# RPI_CAM_INTERFACE.net
KiCad netlist of a schematic drawn in Altium Designer
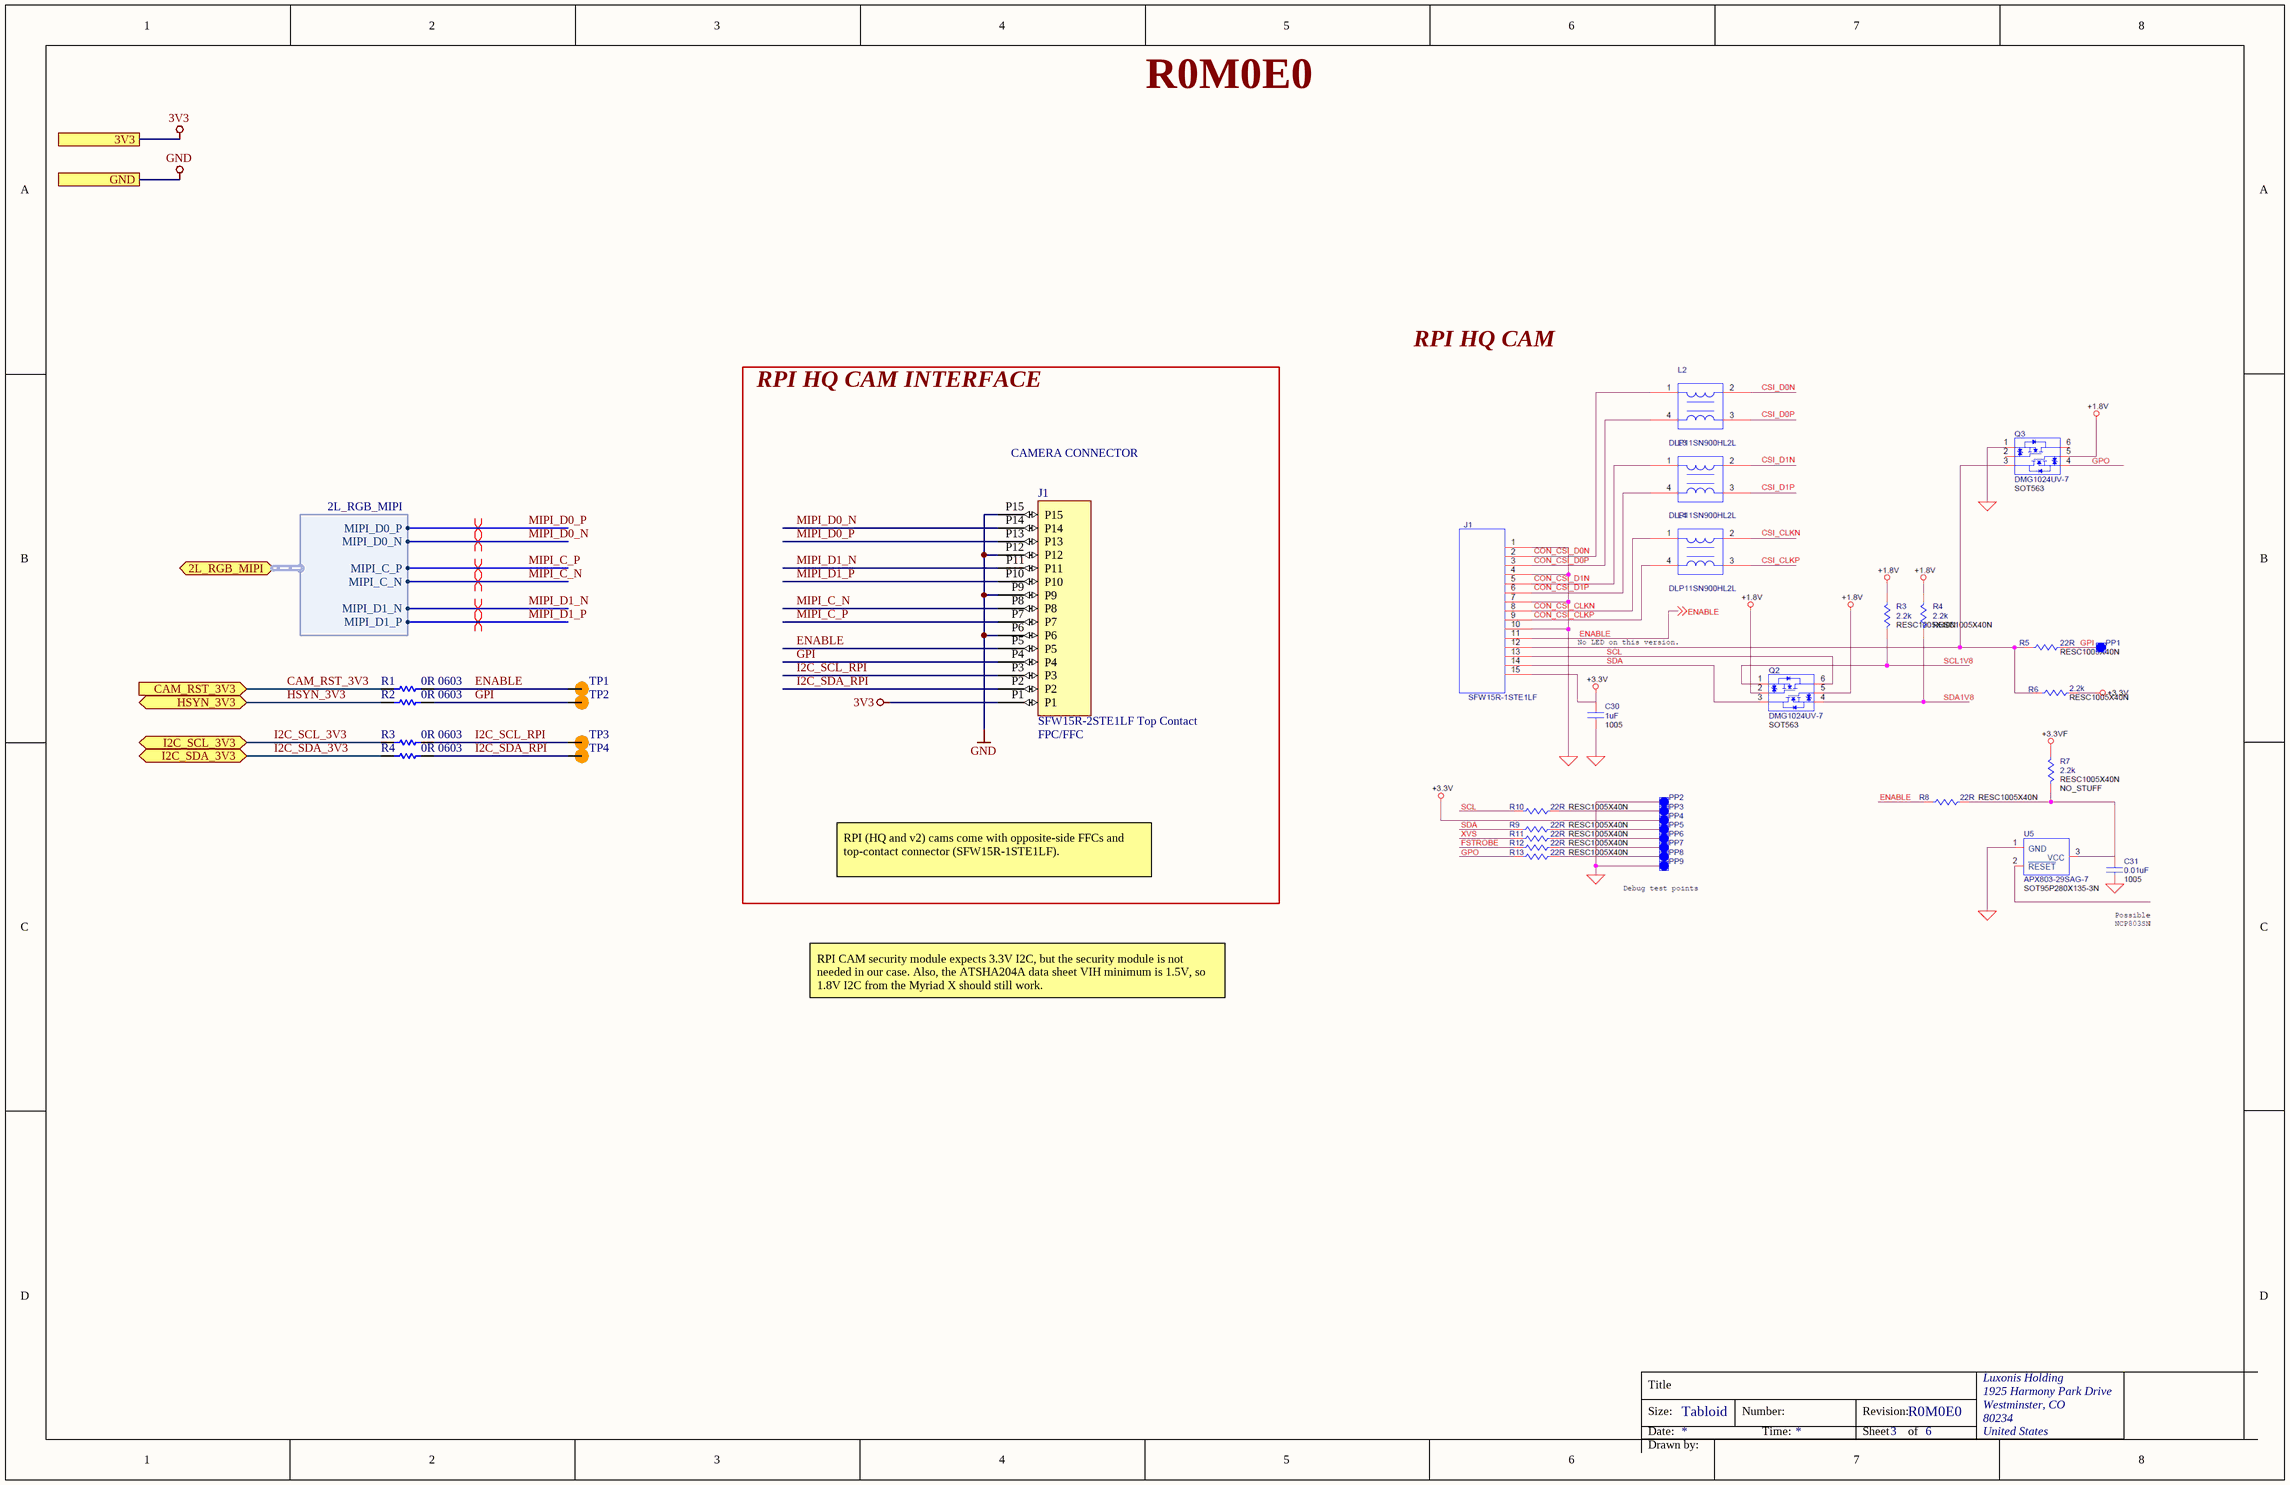
[diagram p0: RPI_CAM_INTERFACE.SchDoc]

(export (version "E")
  (design (tool "Eeschema 10.0.6"))
  (components
    (comp (ref "J1")
      (value "SFW15R-2STE1LF Top Contact")
      (footprint "LuxonisMaster:SFW15R-2STE1LF")
      (description "CONN FFC FPC TOP 15POS 1MM R/A")
      (fields (field (name "MANUFACTURER") "Amphenol") (field (name "COMPONENT SUBTYPE") "FPC/FFC"))
      (libsource (lib "LuxonisMaster") (part "SFW15R-2STE1LF"))
    )
    (comp (ref "R1")
      (value "0R 0603")
      (footprint "RES_Altium_Vault_Generic:RESC0603(1608)_M")
      (fields (field (name "TOLERANCE") "5%"))
      (libsource (lib "LuxonisMaster") (part "CRCW06030000Z0EA"))
    )
    (comp (ref "R2")
      (value "0R 0603")
      (footprint "RES_Altium_Vault_Generic:RESC0603(1608)_M")
      (fields (field (name "TOLERANCE") "5%"))
      (libsource (lib "LuxonisMaster") (part "CRCW06030000Z0EA"))
    )
    (comp (ref "R3")
      (value "0R 0603")
      (footprint "RES_Altium_Vault_Generic:RESC0603(1608)_M")
      (fields (field (name "TOLERANCE") "5%"))
      (libsource (lib "LuxonisMaster") (part "CRCW06030000Z0EA"))
    )
    (comp (ref "R4")
      (value "0R 0603")
      (footprint "RES_Altium_Vault_Generic:RESC0603(1608)_M")
      (fields (field (name "TOLERANCE") "5%"))
      (libsource (lib "LuxonisMaster") (part "CRCW06030000Z0EA"))
    )
    (comp (ref "TP1")
      (value "TP100_150_NS")
      (footprint "LuxonisMaster:TP100_150_NS")
      (libsource (lib "LuxonisMaster") (part "TEST_POINT"))
    )
    (comp (ref "TP2")
      (value "TP100_150_NS")
      (footprint "LuxonisMaster:TP100_150_NS")
      (libsource (lib "LuxonisMaster") (part "TEST_POINT"))
    )
    (comp (ref "TP3")
      (value "TP100_150_NS")
      (footprint "LuxonisMaster:TP100_150_NS")
      (libsource (lib "LuxonisMaster") (part "TEST_POINT"))
    )
    (comp (ref "TP4")
      (value "TP100_150_NS")
      (footprint "LuxonisMaster:TP100_150_NS")
      (libsource (lib "LuxonisMaster") (part "TEST_POINT"))
    )
  )
  (nets
    (net (code "2") (name "/CAM_RST_3V3") (class "Default")
      (node (ref "R1") (pin "1") (pinfunction "1_1") (pintype "passive"))
    )
    (net (code "3") (name "/ENABLE") (class "Default")
      (node (ref "J1") (pin "P5") (pinfunction "P5_P5") (pintype "bidirectional"))
      (node (ref "R1") (pin "2") (pinfunction "2_2") (pintype "passive"))
      (node (ref "TP1") (pin "1") (pintype "passive"))
    )
    (net (code "4") (name "/GPI") (class "Default")
      (node (ref "J1") (pin "P4") (pinfunction "P4_P4") (pintype "bidirectional"))
      (node (ref "R2") (pin "2") (pinfunction "2_2") (pintype "passive"))
      (node (ref "TP2") (pin "1") (pintype "passive"))
    )
    (net (code "5") (name "/HSYN_3V3") (class "Default")
      (node (ref "R2") (pin "1") (pinfunction "1_1") (pintype "passive"))
    )
    (net (code "6") (name "/I2C_SCL_3V3") (class "Default")
      (node (ref "R3") (pin "1") (pinfunction "1_1") (pintype "passive"))
    )
    (net (code "7") (name "/I2C_SCL_RPI") (class "Default")
      (node (ref "J1") (pin "P3") (pinfunction "P3_P3") (pintype "bidirectional"))
      (node (ref "R3") (pin "2") (pinfunction "2_2") (pintype "passive"))
      (node (ref "TP3") (pin "1") (pintype "passive"))
    )
    (net (code "8") (name "/I2C_SDA_3V3") (class "Default")
      (node (ref "R4") (pin "1") (pinfunction "1_1") (pintype "passive"))
    )
    (net (code "9") (name "/I2C_SDA_RPI") (class "Default")
      (node (ref "J1") (pin "P2") (pinfunction "P2_P2") (pintype "bidirectional"))
      (node (ref "R4") (pin "2") (pinfunction "2_2") (pintype "passive"))
      (node (ref "TP4") (pin "1") (pintype "passive"))
    )
    (net (code "10") (name "/MIPI_C_N") (class "Default")
      (node (ref "J1") (pin "P8") (pinfunction "P8_P8") (pintype "bidirectional"))
    )
    (net (code "11") (name "/MIPI_C_P") (class "Default")
      (node (ref "J1") (pin "P7") (pinfunction "P7_P7") (pintype "bidirectional"))
    )
    (net (code "12") (name "/MIPI_D0_N") (class "Default")
      (node (ref "J1") (pin "P14") (pinfunction "P14_P14") (pintype "bidirectional"))
    )
    (net (code "13") (name "/MIPI_D0_P") (class "Default")
      (node (ref "J1") (pin "P13") (pinfunction "P13_P13") (pintype "bidirectional"))
    )
    (net (code "14") (name "/MIPI_D1_N") (class "Default")
      (node (ref "J1") (pin "P11") (pinfunction "P11_P11") (pintype "bidirectional"))
    )
    (net (code "15") (name "/MIPI_D1_P") (class "Default")
      (node (ref "J1") (pin "P10") (pinfunction "P10_P10") (pintype "bidirectional"))
    )
    (net (code "17") (name "3V3") (class "Default")
      (node (ref "J1") (pin "P1") (pinfunction "P1_P1") (pintype "bidirectional"))
    )
    (net (code "18") (name "GND") (class "Default")
      (node (ref "J1") (pin "P12") (pinfunction "P12_P12") (pintype "bidirectional"))
      (node (ref "J1") (pin "P15") (pinfunction "P15_P15") (pintype "bidirectional"))
      (node (ref "J1") (pin "P6") (pinfunction "P6_P6") (pintype "bidirectional"))
      (node (ref "J1") (pin "P9") (pinfunction "P9_P9") (pintype "bidirectional"))
    )
  )
)
